# OPA4227.net
KiCad netlist of a schematic drawn in Altium Designer
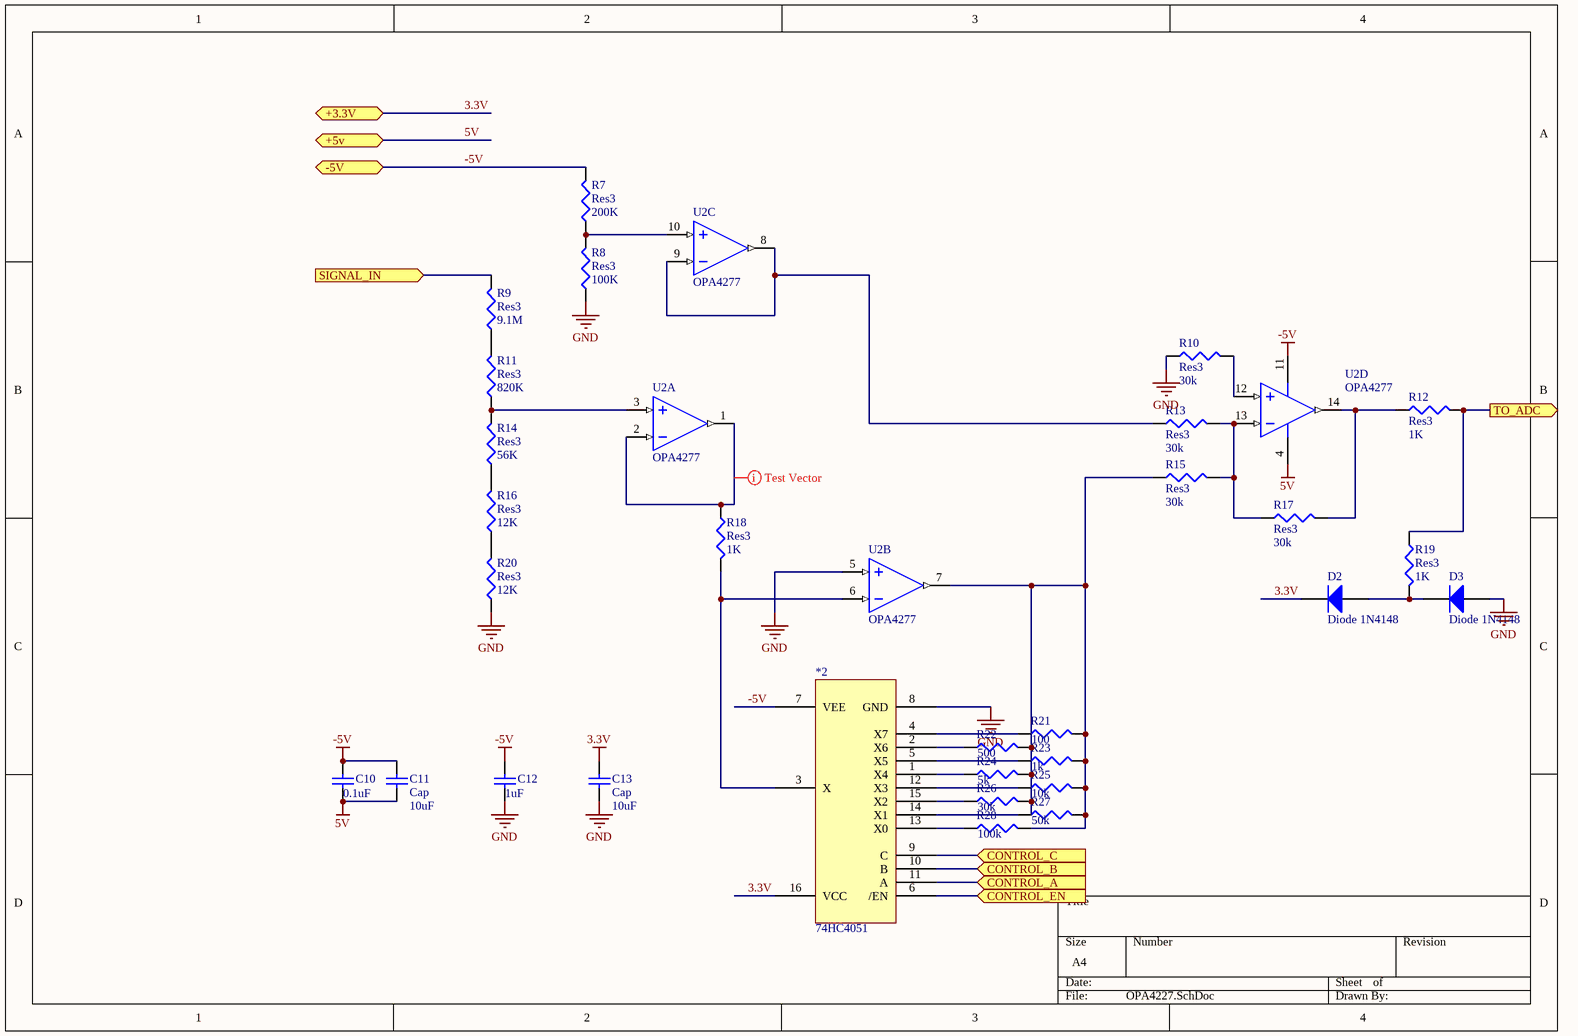
[diagram p0: OPA4227.SchDoc]

(export (version "E")
  (design (tool "Eeschema 10.0.6"))
  (components
    (comp (ref "*2") (value "74HC4051") (footprint "SOP-16") (libsource (lib "SIGNAL") (part "74HC4051")))
    (comp (ref "C10")
      (value "0.1uF")
      (footprint "CAP_0603")
      (description "Capacitor")
      (fields (field (name "Comment") "Cap") (field (name "PUBLISHER") "Altium Limited"))
      (libsource (lib "Miscellaneous Devices") (part "Cap"))
    )
    (comp (ref "C11")
      (value "Cap")
      (footprint "CAP_0603")
      (description "Capacitor")
      (fields (field (name "ALTIUM_VALUE") "10uF") (field (name "PUBLISHER") "Altium Limited"))
      (libsource (lib "Miscellaneous Devices") (part "Cap"))
    )
    (comp (ref "C12")
      (value "1uF")
      (footprint "CAP_0603")
      (description "Capacitor")
      (fields (field (name "Comment") "Cap") (field (name "PUBLISHER") "Altium Limited"))
      (libsource (lib "Miscellaneous Devices") (part "Cap"))
    )
    (comp (ref "C13")
      (value "Cap")
      (footprint "CAP_0603")
      (description "Capacitor")
      (fields (field (name "ALTIUM_VALUE") "10uF") (field (name "PUBLISHER") "Altium Limited"))
      (libsource (lib "Miscellaneous Devices") (part "Cap"))
    )
    (comp (ref "D2")
      (value "Diode 1N4148")
      (footprint "DO-35")
      (description "High Conductance Fast Diode")
      (fields (field (name "PUBLISHER") "Altium Limited"))
      (libsource (lib "Miscellaneous Devices") (part "Diode 1N4148"))
    )
    (comp (ref "D3")
      (value "Diode 1N4148")
      (footprint "DO-35")
      (description "High Conductance Fast Diode")
      (fields (field (name "PUBLISHER") "Altium Limited"))
      (libsource (lib "Miscellaneous Devices") (part "Diode 1N4148"))
    )
    (comp (ref "R7")
      (value "Res3")
      (footprint "RES_0603")
      (description "Resistor")
      (fields (field (name "ALTIUM_VALUE") "200K") (field (name "PUBLISHER") "Altium Limited"))
      (libsource (lib "Miscellaneous Devices") (part "Res3"))
    )
    (comp (ref "R8")
      (value "Res3")
      (footprint "RES_0603")
      (description "Resistor")
      (fields (field (name "ALTIUM_VALUE") "100K") (field (name "PUBLISHER") "Altium Limited"))
      (libsource (lib "Miscellaneous Devices") (part "Res3"))
    )
    (comp (ref "R9")
      (value "Res3")
      (footprint "RES_0603")
      (description "Resistor")
      (fields (field (name "ALTIUM_VALUE") "9.1M") (field (name "PUBLISHER") "Altium Limited"))
      (libsource (lib "Miscellaneous Devices") (part "Res3"))
    )
    (comp (ref "R10")
      (value "Res3")
      (footprint "RES_0603")
      (description "Resistor")
      (fields (field (name "ALTIUM_VALUE") "30k") (field (name "PUBLISHER") "Altium Limited"))
      (libsource (lib "Miscellaneous Devices") (part "Res3"))
    )
    (comp (ref "R11")
      (value "Res3")
      (footprint "RES_0603")
      (description "Resistor")
      (fields (field (name "ALTIUM_VALUE") "820K") (field (name "PUBLISHER") "Altium Limited"))
      (libsource (lib "Miscellaneous Devices") (part "Res3"))
    )
    (comp (ref "R12")
      (value "Res3")
      (footprint "RES_0603")
      (description "Resistor")
      (fields (field (name "ALTIUM_VALUE") "1K") (field (name "PUBLISHER") "Altium Limited"))
      (libsource (lib "Miscellaneous Devices") (part "Res3"))
    )
    (comp (ref "R13")
      (value "Res3")
      (footprint "RES_0603")
      (description "Resistor")
      (fields (field (name "ALTIUM_VALUE") "30k") (field (name "PUBLISHER") "Altium Limited"))
      (libsource (lib "Miscellaneous Devices") (part "Res3"))
    )
    (comp (ref "R14")
      (value "Res3")
      (footprint "RES_0603")
      (description "Resistor")
      (fields (field (name "ALTIUM_VALUE") "56K") (field (name "PUBLISHER") "Altium Limited"))
      (libsource (lib "Miscellaneous Devices") (part "Res3"))
    )
    (comp (ref "R15")
      (value "Res3")
      (footprint "RES_0603")
      (description "Resistor")
      (fields (field (name "ALTIUM_VALUE") "30k") (field (name "PUBLISHER") "Altium Limited"))
      (libsource (lib "Miscellaneous Devices") (part "Res3"))
    )
    (comp (ref "R16")
      (value "Res3")
      (footprint "RES_0603")
      (description "Resistor")
      (fields (field (name "ALTIUM_VALUE") "12K") (field (name "PUBLISHER") "Altium Limited"))
      (libsource (lib "Miscellaneous Devices") (part "Res3"))
    )
    (comp (ref "R17")
      (value "Res3")
      (footprint "RES_0603")
      (description "Resistor")
      (fields (field (name "ALTIUM_VALUE") "30k") (field (name "PUBLISHER") "Altium Limited"))
      (libsource (lib "Miscellaneous Devices") (part "Res3"))
    )
    (comp (ref "R18")
      (value "Res3")
      (footprint "RES_0603")
      (description "Resistor")
      (fields (field (name "ALTIUM_VALUE") "1K") (field (name "PUBLISHER") "Altium Limited"))
      (libsource (lib "Miscellaneous Devices") (part "Res3"))
    )
    (comp (ref "R19")
      (value "Res3")
      (footprint "RES_0603")
      (description "Resistor")
      (fields (field (name "ALTIUM_VALUE") "1K") (field (name "PUBLISHER") "Altium Limited"))
      (libsource (lib "Miscellaneous Devices") (part "Res3"))
    )
    (comp (ref "R20")
      (value "Res3")
      (footprint "RES_0603")
      (description "Resistor")
      (fields (field (name "ALTIUM_VALUE") "12K") (field (name "PUBLISHER") "Altium Limited"))
      (libsource (lib "Miscellaneous Devices") (part "Res3"))
    )
    (comp (ref "R21")
      (value "100")
      (footprint "RES_0603")
      (description "Resistor")
      (fields (field (name "Comment") "Res3") (field (name "PUBLISHER") "Altium Limited"))
      (libsource (lib "Miscellaneous Devices") (part "Res3"))
    )
    (comp (ref "R22")
      (value "500")
      (footprint "RES_0603")
      (description "Resistor")
      (fields (field (name "Comment") "Res3") (field (name "PUBLISHER") "Altium Limited"))
      (libsource (lib "Miscellaneous Devices") (part "Res3"))
    )
    (comp (ref "R23")
      (value "1k")
      (footprint "RES_0603")
      (description "Resistor")
      (fields (field (name "Comment") "Res3") (field (name "PUBLISHER") "Altium Limited"))
      (libsource (lib "Miscellaneous Devices") (part "Res3"))
    )
    (comp (ref "R24")
      (value "5k")
      (footprint "RES_0603")
      (description "Resistor")
      (fields (field (name "Comment") "Res3") (field (name "PUBLISHER") "Altium Limited"))
      (libsource (lib "Miscellaneous Devices") (part "Res3"))
    )
    (comp (ref "R25")
      (value "10k")
      (footprint "RES_0603")
      (description "Resistor")
      (fields (field (name "Comment") "Res3") (field (name "PUBLISHER") "Altium Limited"))
      (libsource (lib "Miscellaneous Devices") (part "Res3"))
    )
    (comp (ref "R26")
      (value "30k")
      (footprint "RES_0603")
      (description "Resistor")
      (fields (field (name "Comment") "Res3") (field (name "PUBLISHER") "Altium Limited"))
      (libsource (lib "Miscellaneous Devices") (part "Res3"))
    )
    (comp (ref "R27")
      (value "50k")
      (footprint "RES_0603")
      (description "Resistor")
      (fields (field (name "Comment") "Res3") (field (name "PUBLISHER") "Altium Limited"))
      (libsource (lib "Miscellaneous Devices") (part "Res3"))
    )
    (comp (ref "R28")
      (value "100k")
      (footprint "RES_0603")
      (description "Resistor")
      (fields (field (name "Comment") "Res3") (field (name "PUBLISHER") "Altium Limited"))
      (libsource (lib "Miscellaneous Devices") (part "Res3"))
    )
    (comp (ref "U2")
      (value "OPA4277")
      (footprint "SO-14")
      (description "High Precision Operational Amplifiers")
      (libsource (lib "SIGNAL") (part "OPA4277"))
    )
  )
  (nets
    (net (code "1") (name "-5V") (class "Default")
      (node (ref "*2") (pin "7") (pinfunction "VEE_7") (pintype "passive"))
      (node (ref "C10") (pin "2") (pinfunction "2_2") (pintype "passive"))
      (node (ref "C11") (pin "2") (pinfunction "2_2") (pintype "passive"))
      (node (ref "C12") (pin "2") (pinfunction "2_2") (pintype "passive"))
      (node (ref "R7") (pin "2") (pinfunction "2_2") (pintype "passive"))
      (node (ref "U2") (pin "11") (pinfunction "V-_11") (pintype "power_in"))
    )
    (net (code "2") (name "/CONTROL_A") (class "Default")
      (node (ref "*2") (pin "11") (pinfunction "A_11") (pintype "passive"))
    )
    (net (code "3") (name "/CONTROL_B") (class "Default")
      (node (ref "*2") (pin "10") (pinfunction "B_10") (pintype "passive"))
    )
    (net (code "4") (name "/CONTROL_C") (class "Default")
      (node (ref "*2") (pin "9") (pinfunction "C_9") (pintype "passive"))
    )
    (net (code "5") (name "/CONTROL_EN") (class "Default")
      (node (ref "*2") (pin "6") (pinfunction "/EN_6") (pintype "passive"))
    )
    (net (code "6") (name "/SIGNAL_IN") (class "Default")
      (node (ref "R9") (pin "2") (pinfunction "2_2") (pintype "passive"))
    )
    (net (code "7") (name "/TO_ADC") (class "Default")
      (node (ref "R12") (pin "2") (pinfunction "2_2") (pintype "passive"))
      (node (ref "R19") (pin "1") (pinfunction "1_1") (pintype "passive"))
    )
    (net (code "8") (name "3.3V") (class "Default")
      (node (ref "*2") (pin "16") (pinfunction "VCC_16") (pintype "passive"))
      (node (ref "C13") (pin "2") (pinfunction "2_2") (pintype "passive"))
      (node (ref "D2") (pin "2") (pinfunction "K_2") (pintype "passive"))
    )
    (net (code "9") (name "5V") (class "Default")
      (node (ref "C10") (pin "1") (pinfunction "1_1") (pintype "passive"))
      (node (ref "C11") (pin "1") (pinfunction "1_1") (pintype "passive"))
      (node (ref "U2") (pin "4") (pinfunction "V+_4") (pintype "power_in"))
    )
    (net (code "10") (name "GND") (class "Default")
      (node (ref "*2") (pin "8") (pinfunction "GND_8") (pintype "passive"))
      (node (ref "C12") (pin "1") (pinfunction "1_1") (pintype "passive"))
      (node (ref "C13") (pin "1") (pinfunction "1_1") (pintype "passive"))
      (node (ref "D3") (pin "1") (pinfunction "A_1") (pintype "passive"))
      (node (ref "R10") (pin "1") (pinfunction "1_1") (pintype "passive"))
      (node (ref "R20") (pin "1") (pinfunction "1_1") (pintype "passive"))
      (node (ref "R8") (pin "1") (pinfunction "1_1") (pintype "passive"))
      (node (ref "U2") (pin "5") (pinfunction "IN+_5") (pintype "input"))
    )
    (net (code "11") (name "Net-(*2-X)") (class "Default")
      (node (ref "*2") (pin "3") (pinfunction "X_3") (pintype "passive"))
      (node (ref "R18") (pin "2") (pinfunction "2_2") (pintype "passive"))
      (node (ref "U2") (pin "6") (pinfunction "IN-_6") (pintype "input"))
    )
    (net (code "12") (name "Net-(*2-X0)") (class "Default")
      (node (ref "*2") (pin "13") (pinfunction "X0_13") (pintype "passive"))
      (node (ref "R28") (pin "1") (pinfunction "1_1") (pintype "passive"))
    )
    (net (code "13") (name "Net-(*2-X1)") (class "Default")
      (node (ref "*2") (pin "14") (pinfunction "X1_14") (pintype "passive"))
      (node (ref "R27") (pin "1") (pinfunction "1_1") (pintype "passive"))
    )
    (net (code "14") (name "Net-(*2-X2)") (class "Default")
      (node (ref "*2") (pin "15") (pinfunction "X2_15") (pintype "passive"))
      (node (ref "R26") (pin "1") (pinfunction "1_1") (pintype "passive"))
    )
    (net (code "15") (name "Net-(*2-X3)") (class "Default")
      (node (ref "*2") (pin "12") (pinfunction "X3_12") (pintype "passive"))
      (node (ref "R25") (pin "1") (pinfunction "1_1") (pintype "passive"))
    )
    (net (code "16") (name "Net-(*2-X4)") (class "Default")
      (node (ref "*2") (pin "1") (pinfunction "X4_1") (pintype "passive"))
      (node (ref "R24") (pin "1") (pinfunction "1_1") (pintype "passive"))
    )
    (net (code "17") (name "Net-(*2-X5)") (class "Default")
      (node (ref "*2") (pin "5") (pinfunction "X5_5") (pintype "passive"))
      (node (ref "R23") (pin "1") (pinfunction "1_1") (pintype "passive"))
    )
    (net (code "18") (name "Net-(*2-X6)") (class "Default")
      (node (ref "*2") (pin "2") (pinfunction "X6_2") (pintype "passive"))
      (node (ref "R22") (pin "1") (pinfunction "1_1") (pintype "passive"))
    )
    (net (code "19") (name "Net-(*2-X7)") (class "Default")
      (node (ref "*2") (pin "4") (pinfunction "X7_4") (pintype "passive"))
      (node (ref "R21") (pin "1") (pinfunction "1_1") (pintype "passive"))
    )
    (net (code "20") (name "Net-(D2-A)") (class "Default")
      (node (ref "D2") (pin "1") (pinfunction "A_1") (pintype "passive"))
      (node (ref "D3") (pin "2") (pinfunction "K_2") (pintype "passive"))
      (node (ref "R19") (pin "2") (pinfunction "2_2") (pintype "passive"))
    )
    (net (code "21") (name "Net-(R11-Pad2)") (class "Default")
      (node (ref "R11") (pin "2") (pinfunction "2_2") (pintype "passive"))
      (node (ref "R9") (pin "1") (pinfunction "1_1") (pintype "passive"))
    )
    (net (code "22") (name "Net-(R14-Pad1)") (class "Default")
      (node (ref "R14") (pin "1") (pinfunction "1_1") (pintype "passive"))
      (node (ref "R16") (pin "2") (pinfunction "2_2") (pintype "passive"))
    )
    (net (code "23") (name "Net-(R16-Pad1)") (class "Default")
      (node (ref "R16") (pin "1") (pinfunction "1_1") (pintype "passive"))
      (node (ref "R20") (pin "2") (pinfunction "2_2") (pintype "passive"))
    )
    (net (code "24") (name "Net-(U2A-IN+)") (class "Default")
      (node (ref "R11") (pin "1") (pinfunction "1_1") (pintype "passive"))
      (node (ref "R14") (pin "2") (pinfunction "2_2") (pintype "passive"))
      (node (ref "U2") (pin "3") (pinfunction "IN+_3") (pintype "input"))
    )
    (net (code "25") (name "Net-(U2A-IN-)") (class "Default")
      (node (ref "R18") (pin "1") (pinfunction "1_1") (pintype "passive"))
      (node (ref "U2") (pin "1") (pinfunction "OUT_1") (pintype "output"))
      (node (ref "U2") (pin "2") (pinfunction "IN-_2") (pintype "input"))
    )
    (net (code "26") (name "Net-(U2B-OUT)") (class "Default")
      (node (ref "R15") (pin "1") (pinfunction "1_1") (pintype "passive"))
      (node (ref "R21") (pin "2") (pinfunction "2_2") (pintype "passive"))
      (node (ref "R22") (pin "2") (pinfunction "2_2") (pintype "passive"))
      (node (ref "R23") (pin "2") (pinfunction "2_2") (pintype "passive"))
      (node (ref "R24") (pin "2") (pinfunction "2_2") (pintype "passive"))
      (node (ref "R25") (pin "2") (pinfunction "2_2") (pintype "passive"))
      (node (ref "R26") (pin "2") (pinfunction "2_2") (pintype "passive"))
      (node (ref "R27") (pin "2") (pinfunction "2_2") (pintype "passive"))
      (node (ref "R28") (pin "2") (pinfunction "2_2") (pintype "passive"))
      (node (ref "U2") (pin "7") (pinfunction "OUT_7") (pintype "output"))
    )
    (net (code "27") (name "Net-(U2C-IN+)") (class "Default")
      (node (ref "R7") (pin "1") (pinfunction "1_1") (pintype "passive"))
      (node (ref "R8") (pin "2") (pinfunction "2_2") (pintype "passive"))
      (node (ref "U2") (pin "10") (pinfunction "IN+_10") (pintype "input"))
    )
    (net (code "28") (name "Net-(U2C-IN-)") (class "Default")
      (node (ref "R13") (pin "1") (pinfunction "1_1") (pintype "passive"))
      (node (ref "U2") (pin "8") (pinfunction "OUT_8") (pintype "output"))
      (node (ref "U2") (pin "9") (pinfunction "IN-_9") (pintype "input"))
    )
    (net (code "29") (name "Net-(U2D-IN+)") (class "Default")
      (node (ref "R10") (pin "2") (pinfunction "2_2") (pintype "passive"))
      (node (ref "U2") (pin "12") (pinfunction "IN+_12") (pintype "input"))
    )
    (net (code "30") (name "Net-(U2D-IN-)") (class "Default")
      (node (ref "R13") (pin "2") (pinfunction "2_2") (pintype "passive"))
      (node (ref "R15") (pin "2") (pinfunction "2_2") (pintype "passive"))
      (node (ref "R17") (pin "1") (pinfunction "1_1") (pintype "passive"))
      (node (ref "U2") (pin "13") (pinfunction "IN-_13") (pintype "input"))
    )
    (net (code "31") (name "Net-(U2D-OUT)") (class "Default")
      (node (ref "R12") (pin "1") (pinfunction "1_1") (pintype "passive"))
      (node (ref "R17") (pin "2") (pinfunction "2_2") (pintype "passive"))
      (node (ref "U2") (pin "14") (pinfunction "OUT_14") (pintype "output"))
    )
  )
)
